# MCU.net
KiCad netlist of a schematic drawn in Altium Designer
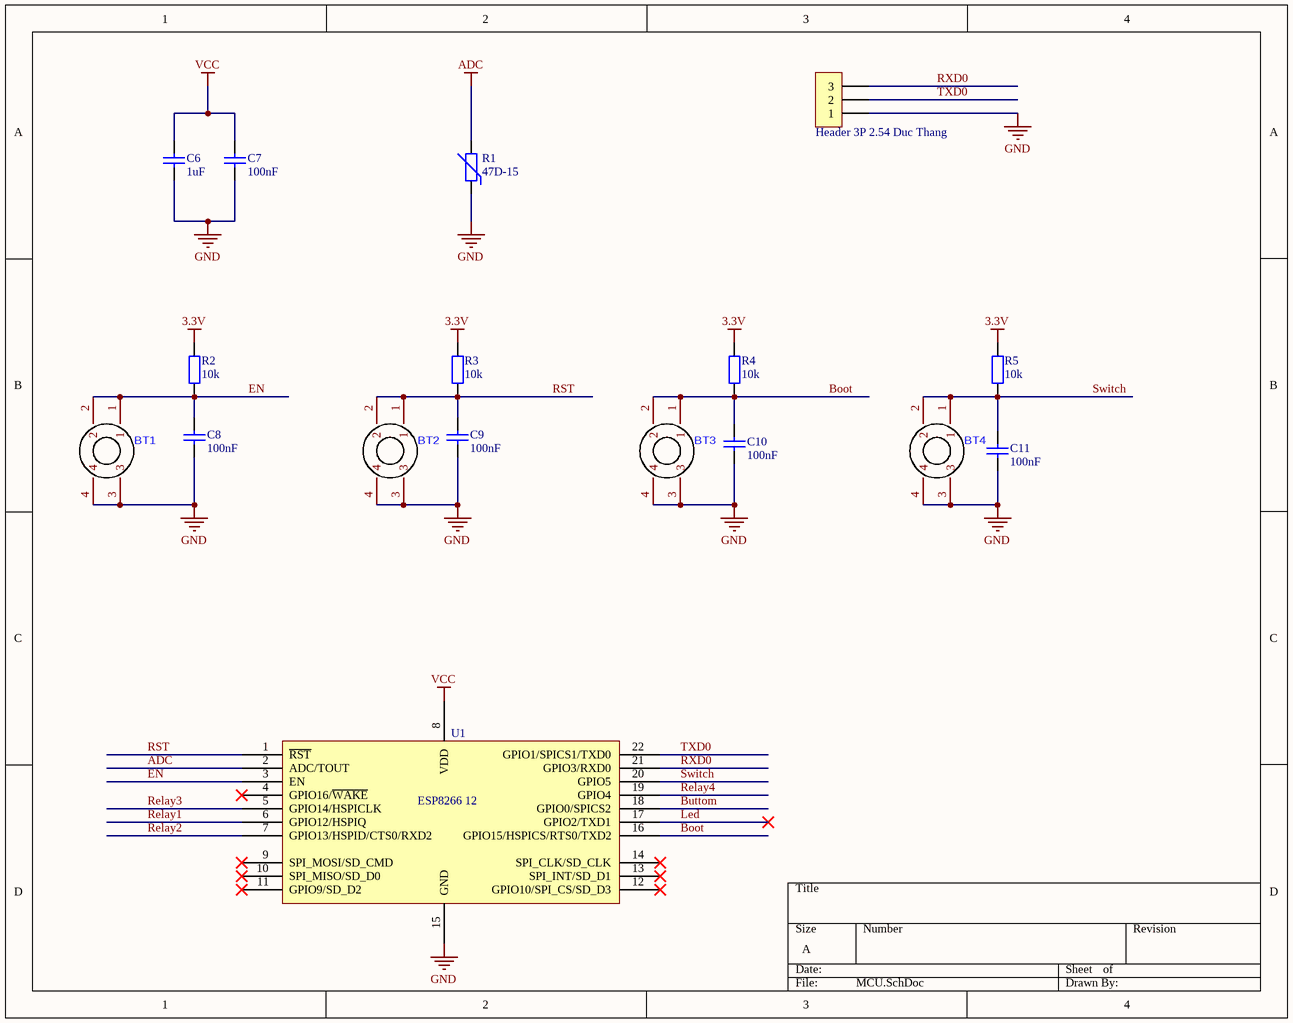
[diagram p0: MCU.SchDoc]

(export (version "E")
  (design (tool "Eeschema 10.0.6"))
  (components
    (comp (ref "BT1")
      (value "Nut Nhan 4 chan 12x12")
      (footprint "12X12 BUTTOM red")
      (libsource (lib "Altium_Lib_by_KhueNguyenCreator") (part "Nut Nhan 4 chan 12x12"))
    )
    (comp (ref "BT2")
      (value "Nut Nhan 4 chan 12x12")
      (footprint "12X12 BUTTOM red")
      (libsource (lib "Altium_Lib_by_KhueNguyenCreator") (part "Nut Nhan 4 chan 12x12"))
    )
    (comp (ref "BT3")
      (value "Nut Nhan 4 chan 12x12")
      (footprint "12X12 BUTTOM red")
      (libsource (lib "Altium_Lib_by_KhueNguyenCreator") (part "Nut Nhan 4 chan 12x12"))
    )
    (comp (ref "BT4")
      (value "Nut Nhan 4 chan 12x12")
      (footprint "12X12 BUTTOM red")
      (libsource (lib "Altium_Lib_by_KhueNguyenCreator") (part "Nut Nhan 4 chan 12x12"))
    )
    (comp (ref "C6")
      (value "1uF")
      (footprint "tu gom")
      (description "Cắm")
      (libsource (lib "Altium_Lib_by_KhueNguyenCreator") (part "Tu gom 15pF 50V"))
    )
    (comp (ref "C7")
      (value "100nF")
      (footprint "tu gom")
      (description "Cắm")
      (libsource (lib "Altium_Lib_by_KhueNguyenCreator") (part "Tu gom 15pF 50V"))
    )
    (comp (ref "C8")
      (value "100nF")
      (footprint "tu gom")
      (description "Cắm")
      (libsource (lib "Altium_Lib_by_KhueNguyenCreator") (part "Tu gom 15pF 50V"))
    )
    (comp (ref "C9")
      (value "100nF")
      (footprint "tu gom")
      (description "Cắm")
      (libsource (lib "Altium_Lib_by_KhueNguyenCreator") (part "Tu gom 15pF 50V"))
    )
    (comp (ref "C10")
      (value "100nF")
      (footprint "tu gom")
      (description "Cắm")
      (libsource (lib "Altium_Lib_by_KhueNguyenCreator") (part "Tu gom 15pF 50V"))
    )
    (comp (ref "C11")
      (value "100nF")
      (footprint "tu gom")
      (description "Cắm")
      (libsource (lib "Altium_Lib_by_KhueNguyenCreator") (part "Tu gom 15pF 50V"))
    )
    (comp (ref "H1")
      (value "Header 3P 2.54 Duc Thang")
      (footprint "XH2.54M-3")
      (description "Cắm")
      (libsource (lib "Altium_Lib_by_KhueNguyenCreator") (part "Header 3P 2.54 Duc Thang"))
    )
    (comp (ref "R1")
      (value "47D-15")
      (footprint "tro nhiet d15")
      (description "Cắm")
      (libsource (lib "Altium_Lib_by_KhueNguyenCreator") (part "Tro Nhiet NTC 47D-15"))
    )
    (comp (ref "R2")
      (value "10k")
      (footprint "tro vach 1/2w")
      (description "Cắm")
      (libsource (lib "Altium_Lib_by_KhueNguyenCreator") (part "Tro Vach 1/2W 5% 47K"))
    )
    (comp (ref "R3")
      (value "10k")
      (footprint "tro vach 1/2w")
      (description "Cắm")
      (libsource (lib "Altium_Lib_by_KhueNguyenCreator") (part "Tro Vach 1/2W 5% 47K"))
    )
    (comp (ref "R4")
      (value "10k")
      (footprint "tro vach 1/2w")
      (description "Cắm")
      (libsource (lib "Altium_Lib_by_KhueNguyenCreator") (part "Tro Vach 1/2W 5% 47K"))
    )
    (comp (ref "R5")
      (value "10k")
      (footprint "tro vach 1/2w")
      (description "Cắm")
      (libsource (lib "Altium_Lib_by_KhueNguyenCreator") (part "Tro Vach 1/2W 5% 47K"))
    )
    (comp (ref "U1")
      (value "ESP8266 12")
      (footprint "ESP8266 12")
      (description "ESP8266 12 22 Pin")
      (libsource (lib "Altium_Lib_by_KhueNguyenCreator") (part "ESP8266 12"))
    )
  )
  (nets
    (net (code "1") (name "/Boot") (class "Default")
      (node (ref "BT3") (pin "1") (pinfunction "1_1") (pintype "passive"))
      (node (ref "BT3") (pin "2") (pinfunction "2_2") (pintype "passive"))
      (node (ref "C10") (pin "1") (pinfunction "1_1") (pintype "passive"))
      (node (ref "R4") (pin "1") (pinfunction "1_1") (pintype "passive"))
      (node (ref "U1") (pin "16") (pinfunction "GPIO15/HSPICS/RTS0/TXD2_16") (pintype "passive"))
    )
    (net (code "2") (name "/Buttom") (class "Default")
      (node (ref "U1") (pin "18") (pinfunction "GPIO0/SPICS2_18") (pintype "passive"))
    )
    (net (code "3") (name "/EN") (class "Default")
      (node (ref "BT1") (pin "1") (pinfunction "1_1") (pintype "passive"))
      (node (ref "BT1") (pin "2") (pinfunction "2_2") (pintype "passive"))
      (node (ref "C8") (pin "1") (pinfunction "1_1") (pintype "passive"))
      (node (ref "R2") (pin "1") (pinfunction "1_1") (pintype "passive"))
      (node (ref "U1") (pin "3") (pinfunction "EN_3") (pintype "passive"))
    )
    (net (code "4") (name "/Led") (class "Default")
      (node (ref "U1") (pin "17") (pinfunction "GPIO2/TXD1_17") (pintype "passive+no_connect"))
    )
    (net (code "5") (name "/RST") (class "Default")
      (node (ref "BT2") (pin "1") (pinfunction "1_1") (pintype "passive"))
      (node (ref "BT2") (pin "2") (pinfunction "2_2") (pintype "passive"))
      (node (ref "C9") (pin "1") (pinfunction "1_1") (pintype "passive"))
      (node (ref "R3") (pin "1") (pinfunction "1_1") (pintype "passive"))
      (node (ref "U1") (pin "1") (pinfunction "~{RST}_1") (pintype "passive"))
    )
    (net (code "6") (name "/RXD0") (class "Default")
      (node (ref "H1") (pin "3") (pinfunction "3_3") (pintype "passive"))
      (node (ref "U1") (pin "21") (pinfunction "GPIO3/RXD0_21") (pintype "passive"))
    )
    (net (code "7") (name "/Relay1") (class "Default")
      (node (ref "U1") (pin "6") (pinfunction "GPIO12/HSPIQ_6") (pintype "passive"))
    )
    (net (code "8") (name "/Relay2") (class "Default")
      (node (ref "U1") (pin "7") (pinfunction "GPIO13/HSPID/CTS0/RXD2_7") (pintype "passive"))
    )
    (net (code "9") (name "/Relay3") (class "Default")
      (node (ref "U1") (pin "5") (pinfunction "GPIO14/HSPICLK_5") (pintype "passive"))
    )
    (net (code "10") (name "/Relay4") (class "Default")
      (node (ref "U1") (pin "19") (pinfunction "GPIO4_19") (pintype "passive"))
    )
    (net (code "11") (name "/Switch") (class "Default")
      (node (ref "BT4") (pin "1") (pinfunction "1_1") (pintype "passive"))
      (node (ref "BT4") (pin "2") (pinfunction "2_2") (pintype "passive"))
      (node (ref "C11") (pin "1") (pinfunction "1_1") (pintype "passive"))
      (node (ref "R5") (pin "1") (pinfunction "1_1") (pintype "passive"))
      (node (ref "U1") (pin "20") (pinfunction "GPIO5_20") (pintype "passive"))
    )
    (net (code "12") (name "/TXD0") (class "Default")
      (node (ref "H1") (pin "2") (pinfunction "2_2") (pintype "passive"))
      (node (ref "U1") (pin "22") (pinfunction "GPIO1/SPICS1/TXD0_22") (pintype "passive"))
    )
    (net (code "13") (name "3.3V") (class "Default")
      (node (ref "R2") (pin "2") (pinfunction "2_2") (pintype "passive"))
      (node (ref "R3") (pin "2") (pinfunction "2_2") (pintype "passive"))
      (node (ref "R4") (pin "2") (pinfunction "2_2") (pintype "passive"))
      (node (ref "R5") (pin "2") (pinfunction "2_2") (pintype "passive"))
    )
    (net (code "14") (name "ADC") (class "Default")
      (node (ref "R1") (pin "2") (pinfunction "2_2") (pintype "passive"))
      (node (ref "U1") (pin "2") (pinfunction "ADC/TOUT_2") (pintype "passive"))
    )
    (net (code "15") (name "GND") (class "Default")
      (node (ref "BT1") (pin "3") (pinfunction "3_3") (pintype "passive"))
      (node (ref "BT1") (pin "4") (pinfunction "4_4") (pintype "passive"))
      (node (ref "BT2") (pin "3") (pinfunction "3_3") (pintype "passive"))
      (node (ref "BT2") (pin "4") (pinfunction "4_4") (pintype "passive"))
      (node (ref "BT3") (pin "3") (pinfunction "3_3") (pintype "passive"))
      (node (ref "BT3") (pin "4") (pinfunction "4_4") (pintype "passive"))
      (node (ref "BT4") (pin "3") (pinfunction "3_3") (pintype "passive"))
      (node (ref "BT4") (pin "4") (pinfunction "4_4") (pintype "passive"))
      (node (ref "C10") (pin "2") (pinfunction "2_2") (pintype "passive"))
      (node (ref "C11") (pin "2") (pinfunction "2_2") (pintype "passive"))
      (node (ref "C6") (pin "2") (pinfunction "2_2") (pintype "passive"))
      (node (ref "C7") (pin "2") (pinfunction "2_2") (pintype "passive"))
      (node (ref "C8") (pin "2") (pinfunction "2_2") (pintype "passive"))
      (node (ref "C9") (pin "2") (pinfunction "2_2") (pintype "passive"))
      (node (ref "H1") (pin "1") (pinfunction "1_1") (pintype "passive"))
      (node (ref "R1") (pin "1") (pinfunction "1_1") (pintype "passive"))
      (node (ref "U1") (pin "15") (pinfunction "GND_15") (pintype "passive"))
    )
    (net (code "16") (name "VCC") (class "Default")
      (node (ref "C6") (pin "1") (pinfunction "1_1") (pintype "passive"))
      (node (ref "C7") (pin "1") (pinfunction "1_1") (pintype "passive"))
      (node (ref "U1") (pin "8") (pinfunction "VDD_8") (pintype "passive"))
    )
    (net (code "17") (name "unconnected-(U1-GPIO9{slash}SD_D2-Pad11)") (class "Default")
      (node (ref "U1") (pin "11") (pinfunction "GPIO9/SD_D2_11") (pintype "passive+no_connect"))
    )
    (net (code "18") (name "unconnected-(U1-GPIO10{slash}SPI_CS{slash}SD_D3-Pad12)") (class "Default")
      (node (ref "U1") (pin "12") (pinfunction "GPIO10/SPI_CS/SD_D3_12") (pintype "passive+no_connect"))
    )
    (net (code "19") (name "unconnected-(U1-GPIO16{slash}~{WAKE}-Pad4)") (class "Default")
      (node (ref "U1") (pin "4") (pinfunction "GPIO16/~{WAKE}_4") (pintype "passive+no_connect"))
    )
    (net (code "20") (name "unconnected-(U1-SPI_CLK{slash}SD_CLK-Pad14)") (class "Default")
      (node (ref "U1") (pin "14") (pinfunction "SPI_CLK/SD_CLK_14") (pintype "passive+no_connect"))
    )
    (net (code "21") (name "unconnected-(U1-SPI_INT{slash}SD_D1-Pad13)") (class "Default")
      (node (ref "U1") (pin "13") (pinfunction "SPI_INT/SD_D1_13") (pintype "passive+no_connect"))
    )
    (net (code "22") (name "unconnected-(U1-SPI_MISO{slash}SD_D0-Pad10)") (class "Default")
      (node (ref "U1") (pin "10") (pinfunction "SPI_MISO/SD_D0_10") (pintype "passive+no_connect"))
    )
    (net (code "23") (name "unconnected-(U1-SPI_MOSI{slash}SD_CMD-Pad9)") (class "Default")
      (node (ref "U1") (pin "9") (pinfunction "SPI_MOSI/SD_CMD_9") (pintype "passive+no_connect"))
    )
  )
)
